# TimeTogetherCounter.net
KiCad netlist of a schematic drawn in Altium Designer
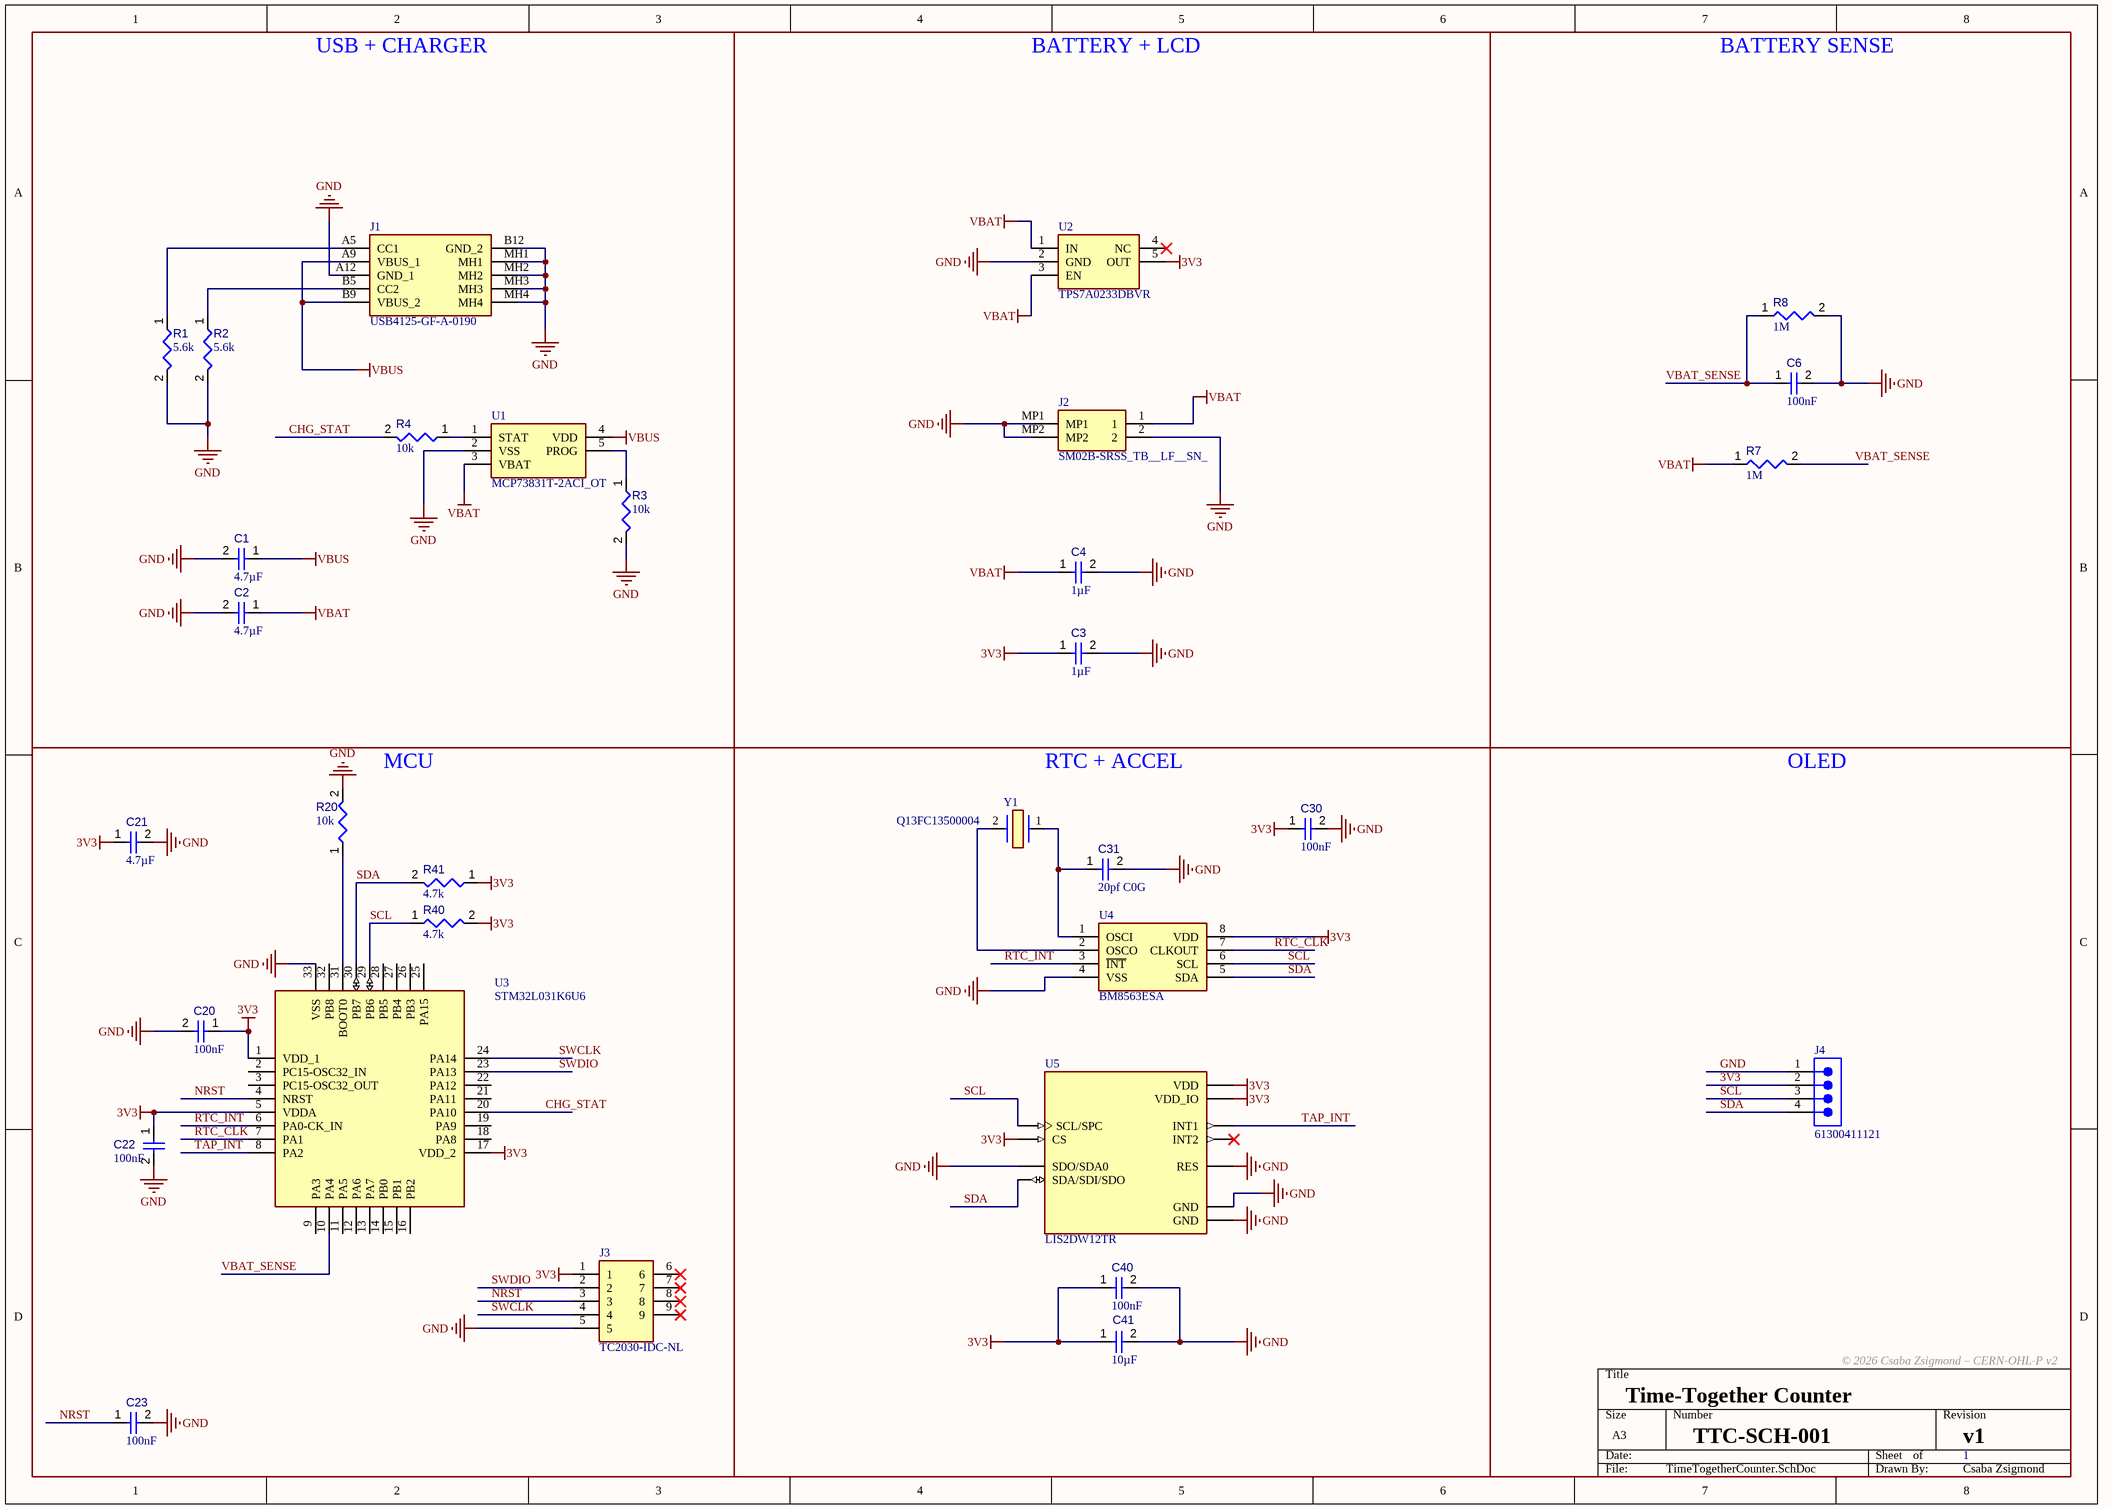
[diagram p0: TimeTogetherCounter.SchDoc]

(export (version "E")
  (design (tool "Eeschema 10.0.6"))
  (components
    (comp (ref "C1")
      (value "4.7µF")
      (footprint "CAPC0603(1608)100_L")
      (description "Chip Capacitor, 4.7µF +/-20%, 10V, 0603, Thickness 1 mm")
      (fields (field (name "TOLERANCE") "10%") (field (name "Comment") "Capacitor 4.7µF +/-20% 10V 0603"))
      (libsource (lib "Zsigmond Csaba") (part "CAP-NP-2"))
    )
    (comp (ref "C2")
      (value "4.7µF")
      (footprint "CAPC0603(1608)100_L")
      (description "Chip Capacitor, 4.7µF +/-20%, 10V, 0603, Thickness 1 mm")
      (fields (field (name "TOLERANCE") "10%") (field (name "Comment") "Capacitor 4.7µF +/-20% 10V 0603"))
      (libsource (lib "Zsigmond Csaba") (part "CAP-NP-2"))
    )
    (comp (ref "C3")
      (value "1µF")
      (footprint "CAPC0402(1005)60_L")
      (description "Chip Capacitor, 1µF +/-20%, 10V, 0402, Thickness 0.6 mm")
      (fields (field (name "TOLERANCE") "10%") (field (name "Comment") "Capacitor 1µF +/-20% 10V 0402"))
      (libsource (lib "Zsigmond Csaba") (part "CAP-NP-2"))
    )
    (comp (ref "C4")
      (value "1µF")
      (footprint "CAPC0402(1005)60_L")
      (description "Chip Capacitor, 1µF +/-20%, 10V, 0402, Thickness 0.6 mm")
      (fields (field (name "TOLERANCE") "10%") (field (name "Comment") "Capacitor 1µF +/-20% 10V 0402"))
      (libsource (lib "Zsigmond Csaba") (part "CAP-NP-2"))
    )
    (comp (ref "C6")
      (value "100nF")
      (footprint "CAPC0402(1005)60_L")
      (description "Chip Capacitor, 100nF +/-20%, 10V, 0402, Thickness 0.6 mm")
      (fields (field (name "TOLERANCE") "20%") (field (name "Comment") "Capacitor 100nF +/-20% 10V 0402"))
      (libsource (lib "Zsigmond Csaba") (part "CAP-NP-2"))
    )
    (comp (ref "C20")
      (value "100nF")
      (footprint "CAPC0402(1005)60_L")
      (description "Chip Capacitor, 100nF +/-20%, 10V, 0402, Thickness 0.6 mm")
      (fields (field (name "TOLERANCE") "20%") (field (name "Comment") "Capacitor 100nF +/-20% 10V 0402"))
      (libsource (lib "Zsigmond Csaba") (part "CAP-NP-2"))
    )
    (comp (ref "C21")
      (value "4.7µF")
      (footprint "CAPC0603(1608)100_L")
      (description "Chip Capacitor, 4.7µF +/-20%, 10V, 0603, Thickness 1 mm")
      (fields (field (name "TOLERANCE") "10%") (field (name "Comment") "Capacitor 4.7µF +/-20% 10V 0603"))
      (libsource (lib "Zsigmond Csaba") (part "CAP-NP-2"))
    )
    (comp (ref "C22")
      (value "100nF")
      (footprint "CAPC0402(1005)60_L")
      (description "Chip Capacitor, 100nF +/-20%, 10V, 0402, Thickness 0.6 mm")
      (fields (field (name "TOLERANCE") "20%") (field (name "Comment") "Capacitor 100nF +/-20% 10V 0402"))
      (libsource (lib "Zsigmond Csaba") (part "CAP-NP-2"))
    )
    (comp (ref "C23")
      (value "100nF")
      (footprint "CAPC0402(1005)60_L")
      (description "Chip Capacitor, 100nF +/-20%, 10V, 0402, Thickness 0.6 mm")
      (fields (field (name "TOLERANCE") "20%") (field (name "Comment") "Capacitor 100nF +/-20% 10V 0402"))
      (libsource (lib "Zsigmond Csaba") (part "CAP-NP-2"))
    )
    (comp (ref "C30")
      (value "100nF")
      (footprint "CAPC0402(1005)60_L")
      (description "Chip Capacitor, 100nF +/-20%, 10V, 0402, Thickness 0.6 mm")
      (fields (field (name "TOLERANCE") "20%") (field (name "Comment") "Capacitor 100nF +/-20% 10V 0402"))
      (libsource (lib "Zsigmond Csaba") (part "CAP-NP-2"))
    )
    (comp (ref "C31")
      (value "20pf C0G")
      (footprint "CAPC0402(1005)60_L")
      (description "Chip Capacitor, 100nF +/-20%, 10V, 0402, Thickness 0.6 mm")
      (fields (field (name "TOLERANCE") "20%") (field (name "Comment") "Capacitor 100nF +/-20% 10V 0402"))
      (libsource (lib "Zsigmond Csaba") (part "CAP-NP-2"))
    )
    (comp (ref "C40")
      (value "100nF")
      (footprint "CAPC0402(1005)60_L")
      (description "Chip Capacitor, 100nF +/-20%, 10V, 0402, Thickness 0.6 mm")
      (fields (field (name "TOLERANCE") "20%") (field (name "Comment") "Capacitor 100nF +/-20% 10V 0402"))
      (libsource (lib "Zsigmond Csaba") (part "CAP-NP-2"))
    )
    (comp (ref "C41")
      (value "10µF")
      (footprint "CAPC0603(1608)100_L")
      (description "Chip Capacitor, 10µF +/-20%, 10V, 0603, Thickness 1 mm")
      (fields (field (name "TOLERANCE") "10%") (field (name "Comment") "Capacitor 10µF +/-20% 10V 0603"))
      (libsource (lib "Zsigmond Csaba") (part "CAP-NP-2"))
    )
    (comp (ref "J1")
      (value "USB4125-GF-A-0190")
      (footprint "SamacSys:USB4125GFA0190")
      (description "Connector")
      (fields (field (name "MOUSER PART NUMBER") "640-USB4125-GF-A-190"))
      (libsource (lib "*") (part "USB4125-GF-A-0190"))
    )
    (comp (ref "J2")
      (value "SM02B-SRSS_TB__LF__SN_")
      (footprint "SamacSys:SM02BSRSSTBLFSN")
      (description "Connector")
      (fields (field (name "MANUFACTURER_PART_NUMBER") "SM02B-SRSS-TB (LF)(SN)"))
      (libsource (lib "*") (part "SM02B-SRSS-TB__LF__SN_"))
    )
    (comp (ref "J3")
      (value "TC2030-IDC-NL")
      (footprint "SamacSys:TC2030IDCNL")
      (description "Connector")
      (libsource (lib "*") (part "TC2030-IDC-NL"))
    )
    (comp (ref "J4")
      (value "61300411121")
      (footprint "61300411121")
      (description "THT Vertical Pin Header WR-PHD, Pitch 2.54 mm, Single Row, 4 pins")
      (libsource (lib "Altium Content Vault") (part "Header_Male_1R_04P"))
    )
    (comp (ref "R1")
      (value "5.6k")
      (footprint "RESC0402(1005)_L")
      (description "5K6 0.063W 5% 0402 (1005 Metric)  SMD")
      (fields (field (name "TOLERANCE") "5%") (field (name "POWER") "63mW"))
      (libsource (lib "Zsigmond Csaba") (part "5D6KR2J"))
    )
    (comp (ref "R2")
      (value "5.6k")
      (footprint "RESC0402(1005)_L")
      (description "5K6 0.063W 5% 0402 (1005 Metric)  SMD")
      (fields (field (name "TOLERANCE") "5%") (field (name "POWER") "63mW"))
      (libsource (lib "Zsigmond Csaba") (part "5D6KR2J"))
    )
    (comp (ref "R3")
      (value "10k")
      (footprint "RESC0402(1005)_L")
      (description "10K 0.063W 1% 0402 (1005 Metric)  SMD")
      (fields (field (name "POWER") "63mW") (field (name "TOLERANCE") "1%"))
      (libsource (lib "Zsigmond Csaba") (part "10KR2F"))
    )
    (comp (ref "R4")
      (value "10k")
      (footprint "RESC0402(1005)_L")
      (description "10K 0.063W 1% 0402 (1005 Metric)  SMD")
      (fields (field (name "POWER") "63mW") (field (name "TOLERANCE") "1%"))
      (libsource (lib "Zsigmond Csaba") (part "10KR2F"))
    )
    (comp (ref "R7")
      (value "1M")
      (footprint "RESC0402(1005)_L")
      (description "Chip Resistor, 1 MOhms, +/-1 %, 63 mW, -55 to 155 degC, 0402")
      (fields (field (name "TOLERANCE") "1%") (field (name "POWER") "63mW"))
      (libsource (lib "Zsigmond Csaba") (part "RES-2"))
    )
    (comp (ref "R8")
      (value "1M")
      (footprint "RESC0402(1005)_L")
      (description "Chip Resistor, 1 MOhms, +/-1 %, 63 mW, -55 to 155 degC, 0402")
      (fields (field (name "TOLERANCE") "1%") (field (name "POWER") "63mW"))
      (libsource (lib "Zsigmond Csaba") (part "RES-2"))
    )
    (comp (ref "R20")
      (value "10k")
      (footprint "RESC0402(1005)_L")
      (description "10K 0.063W 1% 0402 (1005 Metric)  SMD")
      (fields (field (name "POWER") "63mW") (field (name "TOLERANCE") "1%"))
      (libsource (lib "Zsigmond Csaba") (part "10KR2F"))
    )
    (comp (ref "R40")
      (value "4.7k")
      (footprint "RESC0402(1005)_L")
      (description "4K7 0.063W 1% 0402 (1005 Metric)  SMD")
      (fields (field (name "TOLERANCE") "1%") (field (name "POWER") "63mW"))
      (libsource (lib "Zsigmond Csaba") (part "4D7KR2F"))
    )
    (comp (ref "R41")
      (value "4.7k")
      (footprint "RESC0402(1005)_L")
      (description "4K7 0.063W 1% 0402 (1005 Metric)  SMD")
      (fields (field (name "TOLERANCE") "1%") (field (name "POWER") "63mW"))
      (libsource (lib "Zsigmond Csaba") (part "4D7KR2F"))
    )
    (comp (ref "U1")
      (value "MCP73831T-2ACI_OT")
      (footprint "SamacSys:SOT95P270X145-5N")
      (description "Integrated Circuit")
      (fields
        (field (name "MANUFACTURER_PART_NUMBER") "MCP73831T-2ACI/OT")
        (field (name "MOUSER PART NUMBER") "579-MCP73831T-2ACIOT")
      )
      (libsource (lib "*") (part "MCP73831T-2ACI_OT"))
    )
    (comp (ref "U2")
      (value "TPS7A0233DBVR")
      (footprint "SamacSys:SOT95P280X145-5N")
      (description "Integrated Circuit")
      (fields (field (name "MOUSER PART NUMBER") "595-TPS7A0233DBVR"))
      (libsource (lib "*") (part "TPS7A0233DBVR"))
    )
    (comp (ref "U3")
      (value "STM32L031K6U6")
      (footprint "SamacSys:QFN50P500X500X60-33N-D")
      (description "Integrated Circuit")
      (fields (field (name "MOUSER PART NUMBER") "511-STM32L031K6U6"))
      (libsource (lib "SamacSys") (part "STM32L031K6U6"))
    )
    (comp (ref "U4")
      (value "BM8563ESA")
      (footprint "SamacSys:SOIC127P600X175-8N")
      (description "Integrated Circuit")
      (fields (field (name "MANUFACTURER_PART_NUMBER") "PCF8563T"))
      (libsource (lib "*") (part "PCF8563T"))
    )
    (comp (ref "U5")
      (value "LIS2DW12TR")
      (footprint "LGA12R50P4X4_200X200X70")
      (description "Accelerometer X, Y, Z Axis Â±2g, 4g, 8g, 16g 400Hz 12-LGA _2x2_")
      (fields (field (name "MF") "STMicroelectronics"))
      (libsource (lib "SnapEDAsch") (part "LIS2DW12TR"))
    )
    (comp (ref "Y1")
      (value "Q13FC13500004")
      (footprint "SamacSys:Q13FC13500004FC13532768KHZ125PF")
      (description "Crystal or Oscillator")
      (fields (field (name "MANUFACTURER_PART_NUMBER") "Q13FC13500004 FC-135 32.768KHZ 12.5PF"))
      (libsource (lib "*") (part "Q13FC13500004_FC-135_32.768KHZ_12.5PF"))
    )
  )
  (nets
    (net (code "1") (name "/CHG_STAT") (class "Default")
      (node (ref "R4") (pin "2") (pinfunction "2_2") (pintype "passive"))
      (node (ref "U3") (pin "20") (pinfunction "PA10_20") (pintype "passive"))
    )
    (net (code "2") (name "/NRST") (class "Default")
      (node (ref "C23") (pin "1") (pinfunction "1_1") (pintype "passive"))
      (node (ref "J3") (pin "3") (pinfunction "3_3") (pintype "passive"))
      (node (ref "U3") (pin "4") (pinfunction "NRST_4") (pintype "passive"))
    )
    (net (code "3") (name "/RTC_CLK") (class "Default")
      (node (ref "U3") (pin "7") (pinfunction "PA1_7") (pintype "passive"))
      (node (ref "U4") (pin "7") (pinfunction "CLKOUT_7") (pintype "passive"))
    )
    (net (code "4") (name "/RTC_INT") (class "Default")
      (node (ref "U3") (pin "6") (pinfunction "PA0-CK_IN_6") (pintype "passive"))
      (node (ref "U4") (pin "3") (pinfunction "~{INT}_3") (pintype "passive"))
    )
    (net (code "5") (name "/SCL") (class "Default")
      (node (ref "J4") (pin "3") (pinfunction "3_3") (pintype "passive"))
      (node (ref "R40") (pin "1") (pinfunction "1_1") (pintype "passive"))
      (node (ref "U3") (pin "29") (pinfunction "PB6_29") (pintype "bidirectional"))
      (node (ref "U4") (pin "6") (pinfunction "SCL_6") (pintype "passive"))
      (node (ref "U5") (pin "1") (pinfunction "SCL/SPC_1") (pintype "input"))
    )
    (net (code "6") (name "/SDA") (class "Default")
      (node (ref "J4") (pin "4") (pinfunction "4_4") (pintype "passive"))
      (node (ref "R41") (pin "2") (pinfunction "2_2") (pintype "passive"))
      (node (ref "U3") (pin "30") (pinfunction "PB7_30") (pintype "bidirectional"))
      (node (ref "U4") (pin "5") (pinfunction "SDA_5") (pintype "passive"))
      (node (ref "U5") (pin "4") (pinfunction "SDA/SDI/SDO_4") (pintype "bidirectional"))
    )
    (net (code "7") (name "/SWCLK") (class "Default")
      (node (ref "J3") (pin "4") (pinfunction "4_4") (pintype "passive"))
      (node (ref "U3") (pin "24") (pinfunction "PA14_24") (pintype "passive"))
    )
    (net (code "8") (name "/SWDIO") (class "Default")
      (node (ref "J3") (pin "2") (pinfunction "2_2") (pintype "passive"))
      (node (ref "U3") (pin "23") (pinfunction "PA13_23") (pintype "passive"))
    )
    (net (code "9") (name "/TAP_INT") (class "Default")
      (node (ref "U3") (pin "8") (pinfunction "PA2_8") (pintype "passive"))
      (node (ref "U5") (pin "12") (pinfunction "INT1_12") (pintype "output"))
    )
    (net (code "10") (name "/VBAT_SENSE") (class "Default")
      (node (ref "C6") (pin "1") (pinfunction "1_1") (pintype "passive"))
      (node (ref "R7") (pin "2") (pinfunction "2_2") (pintype "passive"))
      (node (ref "R8") (pin "1") (pinfunction "1_1") (pintype "passive"))
      (node (ref "U3") (pin "10") (pinfunction "PA4_10") (pintype "passive"))
    )
    (net (code "11") (name "3V3") (class "Default")
      (node (ref "C20") (pin "1") (pinfunction "1_1") (pintype "passive"))
      (node (ref "C21") (pin "1") (pinfunction "1_1") (pintype "passive"))
      (node (ref "C22") (pin "1") (pinfunction "1_1") (pintype "passive"))
      (node (ref "C3") (pin "1") (pinfunction "1_1") (pintype "passive"))
      (node (ref "C30") (pin "1") (pinfunction "1_1") (pintype "passive"))
      (node (ref "C40") (pin "1") (pinfunction "1_1") (pintype "passive"))
      (node (ref "C41") (pin "1") (pinfunction "1_1") (pintype "passive"))
      (node (ref "J3") (pin "1") (pinfunction "1_1") (pintype "passive"))
      (node (ref "J4") (pin "2") (pinfunction "2_2") (pintype "passive"))
      (node (ref "R40") (pin "2") (pinfunction "2_2") (pintype "passive"))
      (node (ref "R41") (pin "1") (pinfunction "1_1") (pintype "passive"))
      (node (ref "U2") (pin "5") (pinfunction "OUT_5") (pintype "passive"))
      (node (ref "U3") (pin "1") (pinfunction "VDD_1_1") (pintype "passive"))
      (node (ref "U3") (pin "17") (pinfunction "VDD_2_17") (pintype "passive"))
      (node (ref "U3") (pin "5") (pinfunction "VDDA_5") (pintype "passive"))
      (node (ref "U4") (pin "8") (pinfunction "VDD_8") (pintype "passive"))
      (node (ref "U5") (pin "10") (pinfunction "VDD_IO_10") (pintype "power_in"))
      (node (ref "U5") (pin "2") (pinfunction "CS_2") (pintype "input"))
      (node (ref "U5") (pin "9") (pinfunction "VDD_9") (pintype "power_in"))
    )
    (net (code "12") (name "GND") (class "Default")
      (node (ref "C1") (pin "2") (pinfunction "2_2") (pintype "passive"))
      (node (ref "C2") (pin "2") (pinfunction "2_2") (pintype "passive"))
      (node (ref "C20") (pin "2") (pinfunction "2_2") (pintype "passive"))
      (node (ref "C21") (pin "2") (pinfunction "2_2") (pintype "passive"))
      (node (ref "C22") (pin "2") (pinfunction "2_2") (pintype "passive"))
      (node (ref "C23") (pin "2") (pinfunction "2_2") (pintype "passive"))
      (node (ref "C3") (pin "2") (pinfunction "2_2") (pintype "passive"))
      (node (ref "C30") (pin "2") (pinfunction "2_2") (pintype "passive"))
      (node (ref "C31") (pin "2") (pinfunction "2_2") (pintype "passive"))
      (node (ref "C4") (pin "2") (pinfunction "2_2") (pintype "passive"))
      (node (ref "C40") (pin "2") (pinfunction "2_2") (pintype "passive"))
      (node (ref "C41") (pin "2") (pinfunction "2_2") (pintype "passive"))
      (node (ref "C6") (pin "2") (pinfunction "2_2") (pintype "passive"))
      (node (ref "J1") (pin "A12") (pinfunction "GND_1_A12") (pintype "passive"))
      (node (ref "J1") (pin "B12") (pinfunction "GND_2_B12") (pintype "passive"))
      (node (ref "J1") (pin "MH1") (pinfunction "MH1_MH1") (pintype "passive"))
      (node (ref "J1") (pin "MH2") (pinfunction "MH2_MH2") (pintype "passive"))
      (node (ref "J1") (pin "MH3") (pinfunction "MH3_MH3") (pintype "passive"))
      (node (ref "J1") (pin "MH4") (pinfunction "MH4_MH4") (pintype "passive"))
      (node (ref "J2") (pin "2") (pinfunction "2_2") (pintype "passive"))
      (node (ref "J2") (pin "MP1") (pinfunction "MP1_MP1") (pintype "passive"))
      (node (ref "J2") (pin "MP2") (pinfunction "MP2_MP2") (pintype "passive"))
      (node (ref "J3") (pin "5") (pinfunction "5_5") (pintype "passive"))
      (node (ref "J4") (pin "1") (pinfunction "1_1") (pintype "passive"))
      (node (ref "R1") (pin "2") (pinfunction "2_2") (pintype "passive"))
      (node (ref "R2") (pin "2") (pinfunction "2_2") (pintype "passive"))
      (node (ref "R20") (pin "2") (pinfunction "2_2") (pintype "passive"))
      (node (ref "R3") (pin "2") (pinfunction "2_2") (pintype "passive"))
      (node (ref "R8") (pin "2") (pinfunction "2_2") (pintype "passive"))
      (node (ref "U1") (pin "2") (pinfunction "VSS_2") (pintype "passive"))
      (node (ref "U2") (pin "2") (pinfunction "GND_2") (pintype "passive"))
      (node (ref "U3") (pin "33") (pinfunction "VSS_33") (pintype "passive"))
      (node (ref "U4") (pin "4") (pinfunction "VSS_4") (pintype "passive"))
      (node (ref "U5") (pin "3") (pinfunction "SDO/SDA0_3") (pintype "power_in"))
      (node (ref "U5") (pin "6") (pinfunction "GND_6") (pintype "power_in"))
      (node (ref "U5") (pin "7") (pinfunction "RES_7") (pintype "passive"))
      (node (ref "U5") (pin "8") (pinfunction "GND_8") (pintype "power_in"))
    )
    (net (code "13") (name "Net-(J1-CC1)") (class "Default")
      (node (ref "J1") (pin "A5") (pinfunction "CC1_A5") (pintype "passive"))
      (node (ref "R1") (pin "1") (pinfunction "1_1") (pintype "passive"))
    )
    (net (code "14") (name "Net-(J1-CC2)") (class "Default")
      (node (ref "J1") (pin "B5") (pinfunction "CC2_B5") (pintype "passive"))
      (node (ref "R2") (pin "1") (pinfunction "1_1") (pintype "passive"))
    )
    (net (code "15") (name "Net-(U1-PROG)") (class "Default")
      (node (ref "R3") (pin "1") (pinfunction "1_1") (pintype "passive"))
      (node (ref "U1") (pin "5") (pinfunction "PROG_5") (pintype "passive"))
    )
    (net (code "16") (name "Net-(U1-STAT)") (class "Default")
      (node (ref "R4") (pin "1") (pinfunction "1_1") (pintype "passive"))
      (node (ref "U1") (pin "1") (pinfunction "STAT_1") (pintype "passive"))
    )
    (net (code "17") (name "Net-(U3-BOOT0)") (class "Default")
      (node (ref "R20") (pin "1") (pinfunction "1_1") (pintype "passive"))
      (node (ref "U3") (pin "31") (pinfunction "BOOT0_31") (pintype "passive"))
    )
    (net (code "18") (name "Net-(U4-OSCI)") (class "Default")
      (node (ref "C31") (pin "1") (pinfunction "1_1") (pintype "passive"))
      (node (ref "U4") (pin "1") (pinfunction "OSCI_1") (pintype "passive"))
      (node (ref "Y1") (pin "1") (pinfunction "1_1") (pintype "passive"))
    )
    (net (code "19") (name "Net-(U4-OSCO)") (class "Default")
      (node (ref "U4") (pin "2") (pinfunction "OSCO_2") (pintype "passive"))
      (node (ref "Y1") (pin "2") (pinfunction "2_2") (pintype "passive"))
    )
    (net (code "20") (name "VBAT") (class "Default")
      (node (ref "C2") (pin "1") (pinfunction "1_1") (pintype "passive"))
      (node (ref "C4") (pin "1") (pinfunction "1_1") (pintype "passive"))
      (node (ref "J2") (pin "1") (pinfunction "1_1") (pintype "passive"))
      (node (ref "R7") (pin "1") (pinfunction "1_1") (pintype "passive"))
      (node (ref "U1") (pin "3") (pinfunction "VBAT_3") (pintype "passive"))
      (node (ref "U2") (pin "1") (pinfunction "IN_1") (pintype "passive"))
      (node (ref "U2") (pin "3") (pinfunction "EN_3") (pintype "passive"))
    )
    (net (code "21") (name "VBUS") (class "Default")
      (node (ref "C1") (pin "1") (pinfunction "1_1") (pintype "passive"))
      (node (ref "J1") (pin "A9") (pinfunction "VBUS_1_A9") (pintype "passive"))
      (node (ref "J1") (pin "B9") (pinfunction "VBUS_2_B9") (pintype "passive"))
      (node (ref "U1") (pin "4") (pinfunction "VDD_4") (pintype "passive"))
    )
    (net (code "22") (name "unconnected-(J3-Pad6)") (class "Default")
      (node (ref "J3") (pin "6") (pinfunction "6_6") (pintype "passive+no_connect"))
    )
    (net (code "23") (name "unconnected-(J3-Pad7)") (class "Default")
      (node (ref "J3") (pin "7") (pinfunction "7_7") (pintype "passive+no_connect"))
    )
    (net (code "24") (name "unconnected-(J3-Pad8)") (class "Default")
      (node (ref "J3") (pin "8") (pinfunction "8_8") (pintype "passive+no_connect"))
    )
    (net (code "25") (name "unconnected-(J3-Pad9)") (class "Default")
      (node (ref "J3") (pin "9") (pinfunction "9_9") (pintype "passive+no_connect"))
    )
    (net (code "26") (name "unconnected-(U2-NC-Pad4)") (class "Default")
      (node (ref "U2") (pin "4") (pinfunction "NC_4") (pintype "passive+no_connect"))
    )
    (net (code "27") (name "unconnected-(U3-PA3-Pad9)") (class "Default")
      (node (ref "U3") (pin "9") (pinfunction "PA3_9") (pintype "passive"))
    )
    (net (code "28") (name "unconnected-(U3-PA5-Pad11)") (class "Default")
      (node (ref "U3") (pin "11") (pinfunction "PA5_11") (pintype "passive"))
    )
    (net (code "29") (name "unconnected-(U3-PA6-Pad12)") (class "Default")
      (node (ref "U3") (pin "12") (pinfunction "PA6_12") (pintype "passive"))
    )
    (net (code "30") (name "unconnected-(U3-PA7-Pad13)") (class "Default")
      (node (ref "U3") (pin "13") (pinfunction "PA7_13") (pintype "passive"))
    )
    (net (code "31") (name "unconnected-(U3-PA8-Pad18)") (class "Default")
      (node (ref "U3") (pin "18") (pinfunction "PA8_18") (pintype "passive"))
    )
    (net (code "32") (name "unconnected-(U3-PA9-Pad19)") (class "Default")
      (node (ref "U3") (pin "19") (pinfunction "PA9_19") (pintype "passive"))
    )
    (net (code "33") (name "unconnected-(U3-PA11-Pad21)") (class "Default")
      (node (ref "U3") (pin "21") (pinfunction "PA11_21") (pintype "passive"))
    )
    (net (code "34") (name "unconnected-(U3-PA12-Pad22)") (class "Default")
      (node (ref "U3") (pin "22") (pinfunction "PA12_22") (pintype "passive"))
    )
    (net (code "35") (name "unconnected-(U3-PA15-Pad25)") (class "Default")
      (node (ref "U3") (pin "25") (pinfunction "PA15_25") (pintype "passive"))
    )
    (net (code "36") (name "unconnected-(U3-PB0-Pad14)") (class "Default")
      (node (ref "U3") (pin "14") (pinfunction "PB0_14") (pintype "passive"))
    )
    (net (code "37") (name "unconnected-(U3-PB1-Pad15)") (class "Default")
      (node (ref "U3") (pin "15") (pinfunction "PB1_15") (pintype "passive"))
    )
    (net (code "38") (name "unconnected-(U3-PB2-Pad16)") (class "Default")
      (node (ref "U3") (pin "16") (pinfunction "PB2_16") (pintype "passive"))
    )
    (net (code "39") (name "unconnected-(U3-PB3-Pad26)") (class "Default")
      (node (ref "U3") (pin "26") (pinfunction "PB3_26") (pintype "passive"))
    )
    (net (code "40") (name "unconnected-(U3-PB4-Pad27)") (class "Default")
      (node (ref "U3") (pin "27") (pinfunction "PB4_27") (pintype "passive"))
    )
    (net (code "41") (name "unconnected-(U3-PB5-Pad28)") (class "Default")
      (node (ref "U3") (pin "28") (pinfunction "PB5_28") (pintype "passive"))
    )
    (net (code "42") (name "unconnected-(U3-PB8-Pad32)") (class "Default")
      (node (ref "U3") (pin "32") (pinfunction "PB8_32") (pintype "passive"))
    )
    (net (code "43") (name "unconnected-(U3-PC15-OSC32_IN-Pad2)") (class "Default")
      (node (ref "U3") (pin "2") (pinfunction "PC15-OSC32_IN_2") (pintype "passive"))
    )
    (net (code "44") (name "unconnected-(U3-PC15-OSC32_OUT-Pad3)") (class "Default")
      (node (ref "U3") (pin "3") (pinfunction "PC15-OSC32_OUT_3") (pintype "passive"))
    )
    (net (code "45") (name "unconnected-(U5-INT2-Pad11)") (class "Default")
      (node (ref "U5") (pin "11") (pinfunction "INT2_11") (pintype "output+no_connect"))
    )
  )
)
